# 03_-_28PINS_SCHEMATIC.net
KiCad netlist of a schematic drawn in Altium Designer
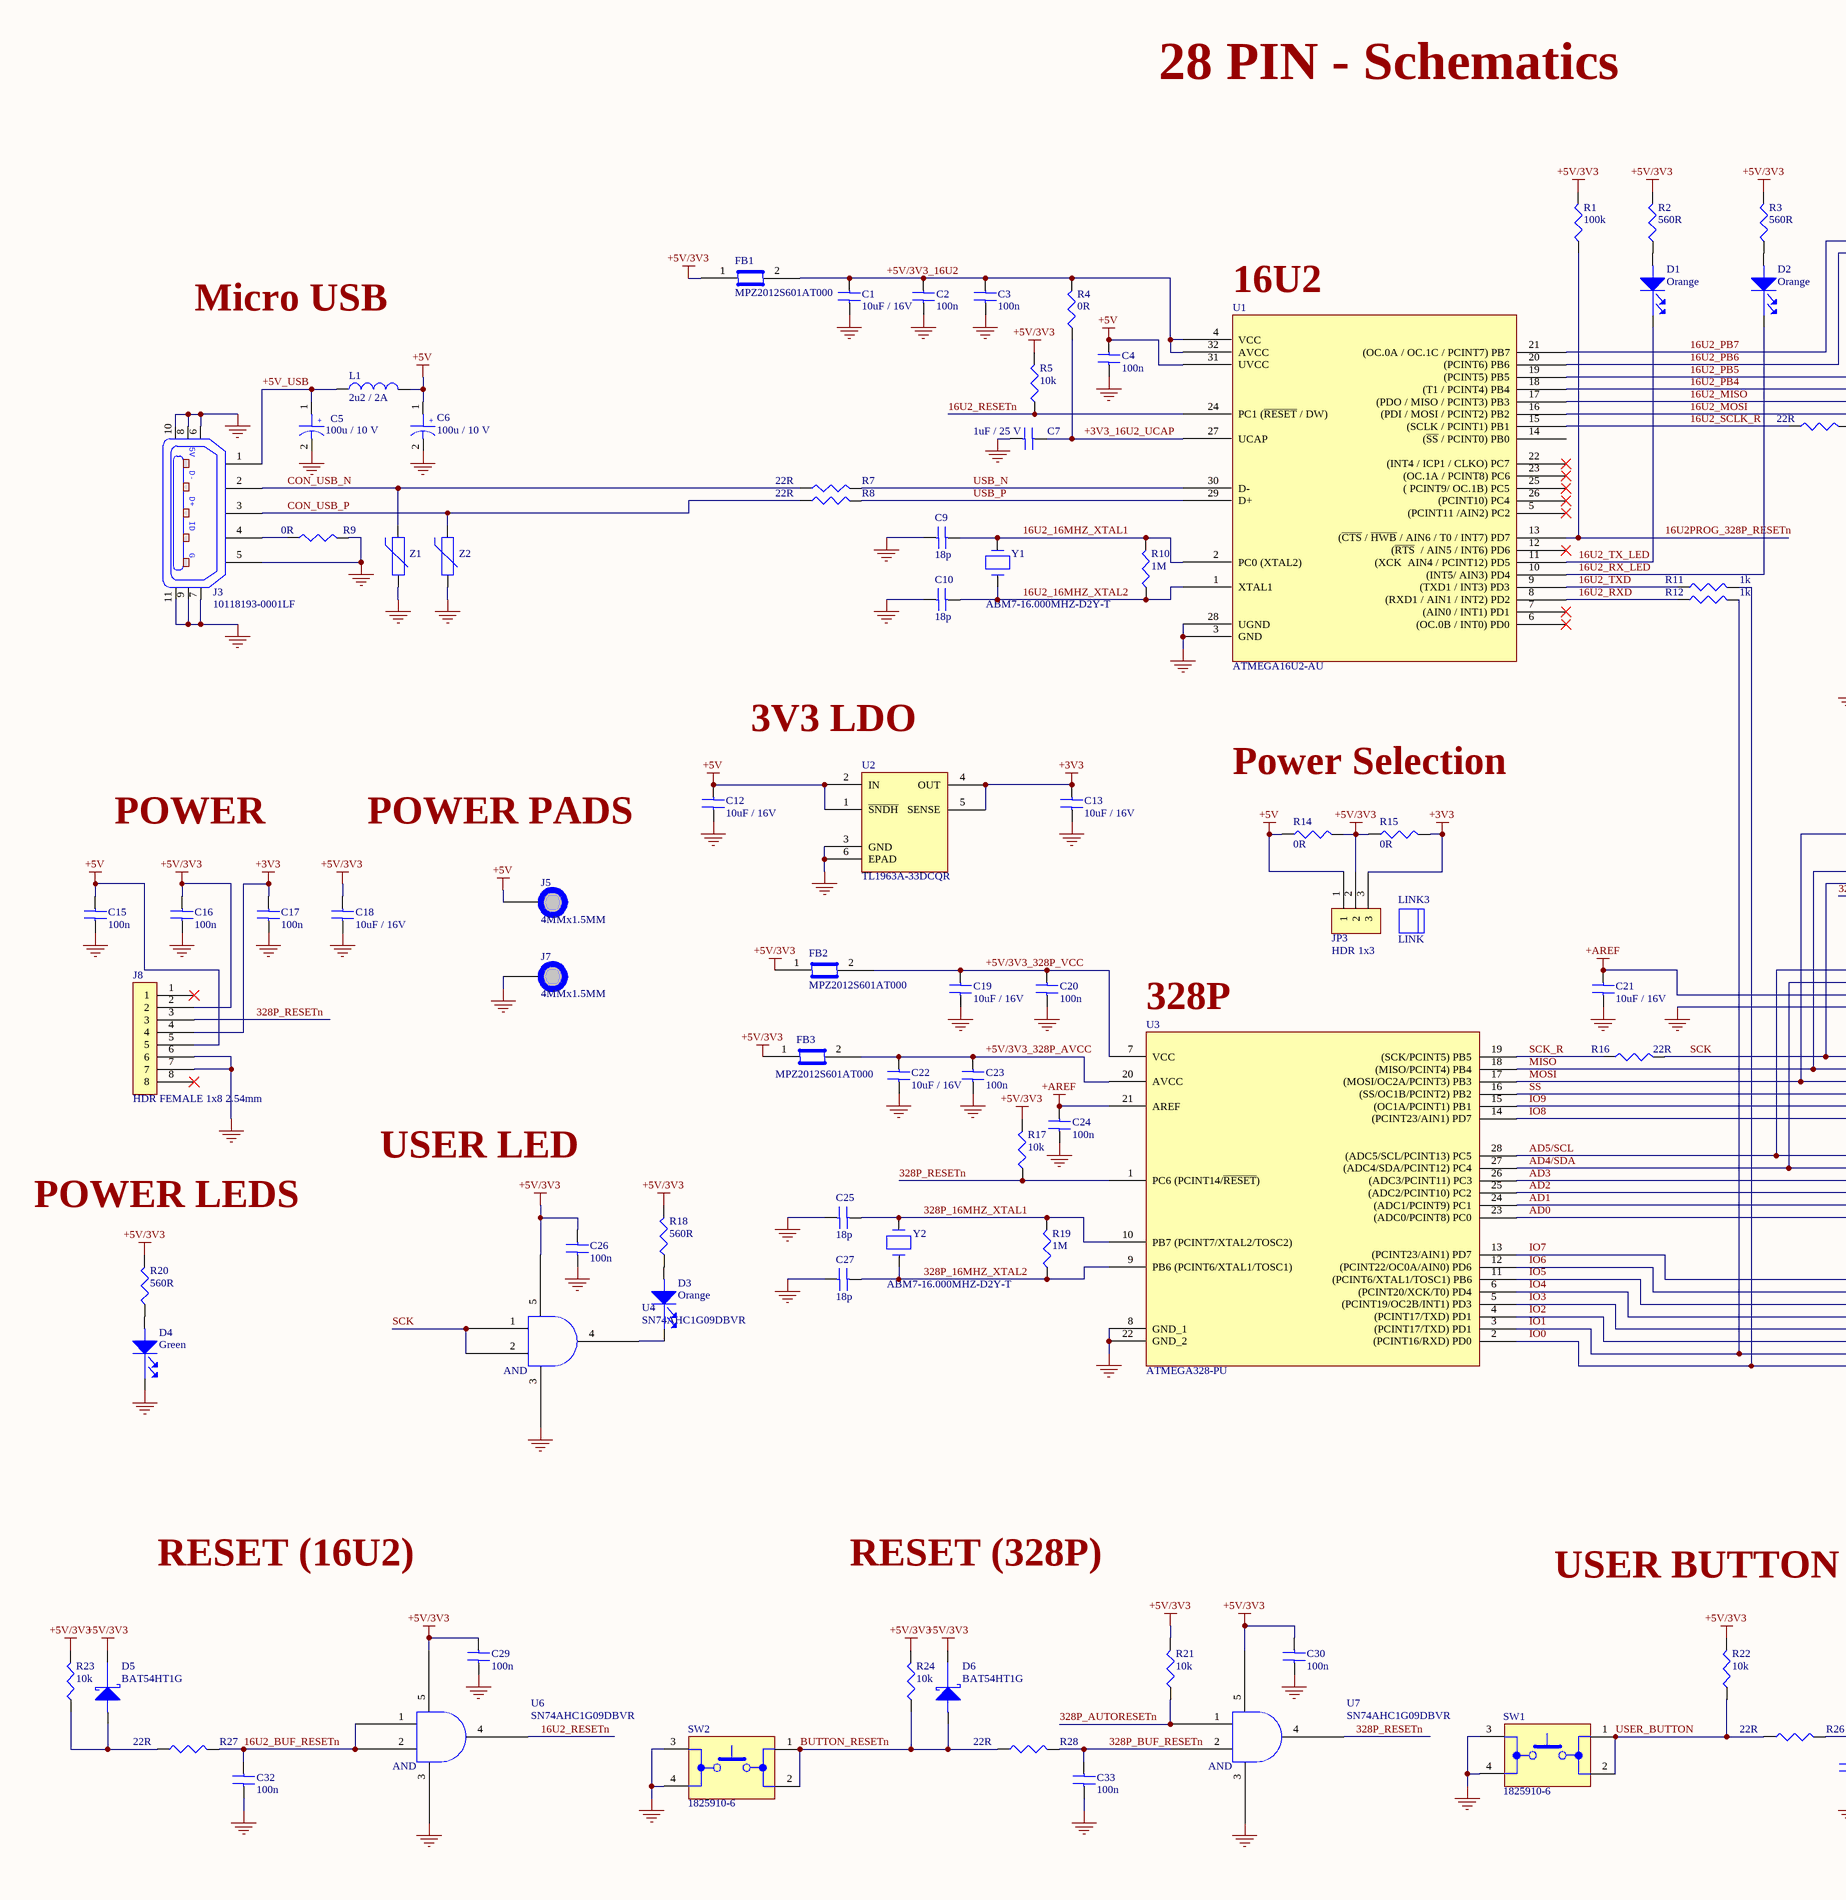
[diagram p0: [03] - 28PINS SCHEMATIC.SchDoc, left]
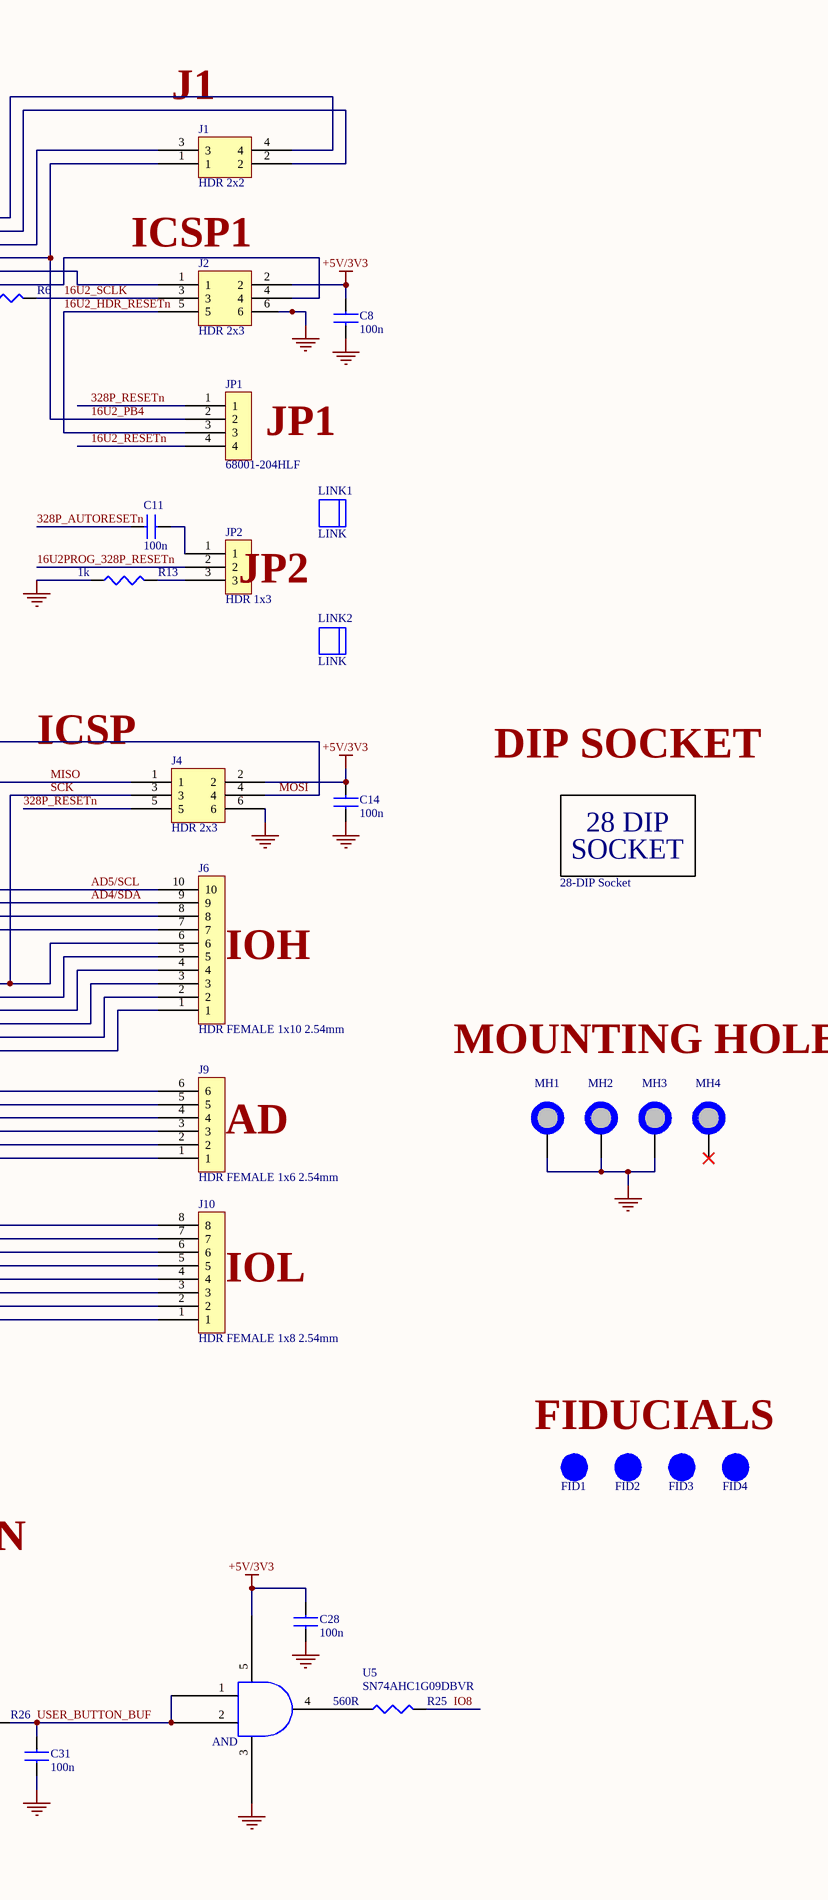
[diagram p1: [03] - 28PINS SCHEMATIC.SchDoc, right]

(export (version "E")
  (design (tool "Eeschema 10.0.6"))
  (components
    (comp (ref "C1")
      (value "10uF / 16V")
      (footprint "C0805")
      (fields
        (field (name "MANUFACTURER") "TDK")
        (field (name "MANUFACTURER PART NUMBER") "C2012X5R1C106M125AC")
        (field (name "TOLERANCE") "20%")
      )
      (libsource (lib "28_Pins_Project_V1I2") (part "C2012X5R1C106M125AC"))
    )
    (comp (ref "C2")
      (value "100n")
      (footprint "C0805")
      (fields
        (field (name "MANUFACTURER") "TDK")
        (field (name "MANUFACTURER PART NUMBER") "C2012X7R1H104K085AA")
        (field (name "TOLERANCE") "10%")
      )
      (libsource (lib "28_Pins_Project_V1I2") (part "C2012X7R1H104K085AA"))
    )
    (comp (ref "C3")
      (value "100n")
      (footprint "C0805")
      (fields
        (field (name "MANUFACTURER") "TDK")
        (field (name "MANUFACTURER PART NUMBER") "C2012X7R1H104K085AA")
        (field (name "TOLERANCE") "10%")
      )
      (libsource (lib "28_Pins_Project_V1I2") (part "C2012X7R1H104K085AA"))
    )
    (comp (ref "C4")
      (value "100n")
      (footprint "C0805")
      (fields
        (field (name "MANUFACTURER") "TDK")
        (field (name "MANUFACTURER PART NUMBER") "C2012X7R1H104K085AA")
        (field (name "TOLERANCE") "10%")
      )
      (libsource (lib "28_Pins_Project_V1I2") (part "C2012X7R1H104K085AA"))
    )
    (comp (ref "C5")
      (value "100u / 10 V")
      (footprint "C_ALU_C_SIZE")
      (description "CAP ALUM 100UF 20% 10V SMD")
      (fields
        (field (name "MANUFACTURER") "Panasonic")
        (field (name "MANUFACTURER PART NUMBER") "EEE-1AA101WR")
      )
      (libsource (lib "28_Pins_Project_V1I2") (part "EEE-1AA101WR"))
    )
    (comp (ref "C6")
      (value "100u / 10 V")
      (footprint "C_ALU_C_SIZE")
      (description "CAP ALUM 100UF 20% 10V SMD")
      (fields
        (field (name "MANUFACTURER") "Panasonic")
        (field (name "MANUFACTURER PART NUMBER") "EEE-1AA101WR")
      )
      (libsource (lib "28_Pins_Project_V1I2") (part "EEE-1AA101WR"))
    )
    (comp (ref "C7")
      (value "1uF / 25 V")
      (footprint "C0805")
      (fields
        (field (name "MANUFACTURER") "TDK")
        (field (name "MANUFACTURER PART NUMBER") "C2012X5R1E105K125AA")
        (field (name "TOLERANCE") "10%")
      )
      (libsource (lib "28_Pins_Project_V1I2") (part "C2012X5R1E105K125AA"))
    )
    (comp (ref "C8")
      (value "100n")
      (footprint "C0805")
      (fields
        (field (name "MANUFACTURER") "TDK")
        (field (name "MANUFACTURER PART NUMBER") "C2012X7R1H104K085AA")
        (field (name "TOLERANCE") "10%")
      )
      (libsource (lib "28_Pins_Project_V1I2") (part "C2012X7R1H104K085AA"))
    )
    (comp (ref "C9")
      (value "18p")
      (footprint "C0805")
      (description "CAP CER 18PF 50V C0G/NP0 0805")
      (fields
        (field (name "MANUFACTURER") "KEMET")
        (field (name "MANUFACTURER PART NUMBER") "C0805C180J5GACTU")
      )
      (libsource (lib "28_Pins_Project_V1I2") (part "C0805C180J5GACTU"))
    )
    (comp (ref "C10")
      (value "18p")
      (footprint "C0805")
      (description "CAP CER 18PF 50V C0G/NP0 0805")
      (fields
        (field (name "MANUFACTURER") "KEMET")
        (field (name "MANUFACTURER PART NUMBER") "C0805C180J5GACTU")
      )
      (libsource (lib "28_Pins_Project_V1I2") (part "C0805C180J5GACTU"))
    )
    (comp (ref "C11")
      (value "100n")
      (footprint "C0805")
      (fields
        (field (name "MANUFACTURER") "TDK")
        (field (name "MANUFACTURER PART NUMBER") "C2012X7R1H104K085AA")
        (field (name "TOLERANCE") "10%")
      )
      (libsource (lib "28_Pins_Project_V1I2") (part "C2012X7R1H104K085AA"))
    )
    (comp (ref "C12")
      (value "10uF / 16V")
      (footprint "C0805")
      (fields
        (field (name "MANUFACTURER") "TDK")
        (field (name "MANUFACTURER PART NUMBER") "C2012X5R1C106M125AC")
        (field (name "TOLERANCE") "20%")
      )
      (libsource (lib "28_Pins_Project_V1I2") (part "C2012X5R1C106M125AC"))
    )
    (comp (ref "C13")
      (value "10uF / 16V")
      (footprint "C0805")
      (fields
        (field (name "MANUFACTURER") "TDK")
        (field (name "MANUFACTURER PART NUMBER") "C2012X5R1C106M125AC")
        (field (name "TOLERANCE") "20%")
      )
      (libsource (lib "28_Pins_Project_V1I2") (part "C2012X5R1C106M125AC"))
    )
    (comp (ref "C14")
      (value "100n")
      (footprint "C0805")
      (fields
        (field (name "MANUFACTURER") "TDK")
        (field (name "MANUFACTURER PART NUMBER") "C2012X7R1H104K085AA")
        (field (name "TOLERANCE") "10%")
      )
      (libsource (lib "28_Pins_Project_V1I2") (part "C2012X7R1H104K085AA"))
    )
    (comp (ref "C15")
      (value "100n")
      (footprint "C0805")
      (fields
        (field (name "MANUFACTURER") "TDK")
        (field (name "MANUFACTURER PART NUMBER") "C2012X7R1H104K085AA")
        (field (name "TOLERANCE") "10%")
      )
      (libsource (lib "28_Pins_Project_V1I2") (part "C2012X7R1H104K085AA"))
    )
    (comp (ref "C16")
      (value "100n")
      (footprint "C0805")
      (fields
        (field (name "MANUFACTURER") "TDK")
        (field (name "MANUFACTURER PART NUMBER") "C2012X7R1H104K085AA")
        (field (name "TOLERANCE") "10%")
      )
      (libsource (lib "28_Pins_Project_V1I2") (part "C2012X7R1H104K085AA"))
    )
    (comp (ref "C17")
      (value "100n")
      (footprint "C0805")
      (fields
        (field (name "MANUFACTURER") "TDK")
        (field (name "MANUFACTURER PART NUMBER") "C2012X7R1H104K085AA")
        (field (name "TOLERANCE") "10%")
      )
      (libsource (lib "28_Pins_Project_V1I2") (part "C2012X7R1H104K085AA"))
    )
    (comp (ref "C18")
      (value "10uF / 16V")
      (footprint "C0805")
      (fields
        (field (name "MANUFACTURER") "TDK")
        (field (name "MANUFACTURER PART NUMBER") "C2012X5R1C106M125AC")
        (field (name "TOLERANCE") "20%")
      )
      (libsource (lib "28_Pins_Project_V1I2") (part "C2012X5R1C106M125AC"))
    )
    (comp (ref "C19")
      (value "10uF / 16V")
      (footprint "C0805")
      (fields
        (field (name "MANUFACTURER") "TDK")
        (field (name "MANUFACTURER PART NUMBER") "C2012X5R1C106M125AC")
        (field (name "TOLERANCE") "20%")
      )
      (libsource (lib "28_Pins_Project_V1I2") (part "C2012X5R1C106M125AC"))
    )
    (comp (ref "C20")
      (value "100n")
      (footprint "C0805")
      (fields
        (field (name "MANUFACTURER") "TDK")
        (field (name "MANUFACTURER PART NUMBER") "C2012X7R1H104K085AA")
        (field (name "TOLERANCE") "10%")
      )
      (libsource (lib "28_Pins_Project_V1I2") (part "C2012X7R1H104K085AA"))
    )
    (comp (ref "C21")
      (value "10uF / 16V")
      (footprint "C0805")
      (fields
        (field (name "MANUFACTURER") "TDK")
        (field (name "MANUFACTURER PART NUMBER") "C2012X5R1C106M125AC")
        (field (name "TOLERANCE") "20%")
      )
      (libsource (lib "28_Pins_Project_V1I2") (part "C2012X5R1C106M125AC"))
    )
    (comp (ref "C22")
      (value "10uF / 16V")
      (footprint "C0805")
      (fields
        (field (name "MANUFACTURER") "TDK")
        (field (name "MANUFACTURER PART NUMBER") "C2012X5R1C106M125AC")
        (field (name "TOLERANCE") "20%")
      )
      (libsource (lib "28_Pins_Project_V1I2") (part "C2012X5R1C106M125AC"))
    )
    (comp (ref "C23")
      (value "100n")
      (footprint "C0805")
      (fields
        (field (name "MANUFACTURER") "TDK")
        (field (name "MANUFACTURER PART NUMBER") "C2012X7R1H104K085AA")
        (field (name "TOLERANCE") "10%")
      )
      (libsource (lib "28_Pins_Project_V1I2") (part "C2012X7R1H104K085AA"))
    )
    (comp (ref "C24")
      (value "100n")
      (footprint "C0805")
      (fields
        (field (name "MANUFACTURER") "TDK")
        (field (name "MANUFACTURER PART NUMBER") "C2012X7R1H104K085AA")
        (field (name "TOLERANCE") "10%")
      )
      (libsource (lib "28_Pins_Project_V1I2") (part "C2012X7R1H104K085AA"))
    )
    (comp (ref "C25")
      (value "18p")
      (footprint "C0805")
      (description "CAP CER 18PF 50V C0G/NP0 0805")
      (fields
        (field (name "MANUFACTURER") "KEMET")
        (field (name "MANUFACTURER PART NUMBER") "C0805C180J5GACTU")
      )
      (libsource (lib "28_Pins_Project_V1I2") (part "C0805C180J5GACTU"))
    )
    (comp (ref "C26")
      (value "100n")
      (footprint "C0805")
      (fields
        (field (name "MANUFACTURER") "TDK")
        (field (name "MANUFACTURER PART NUMBER") "C2012X7R1H104K085AA")
        (field (name "TOLERANCE") "10%")
      )
      (libsource (lib "28_Pins_Project_V1I2") (part "C2012X7R1H104K085AA"))
    )
    (comp (ref "C27")
      (value "18p")
      (footprint "C0805")
      (description "CAP CER 18PF 50V C0G/NP0 0805")
      (fields
        (field (name "MANUFACTURER") "KEMET")
        (field (name "MANUFACTURER PART NUMBER") "C0805C180J5GACTU")
      )
      (libsource (lib "28_Pins_Project_V1I2") (part "C0805C180J5GACTU"))
    )
    (comp (ref "C28")
      (value "100n")
      (footprint "C0805")
      (fields
        (field (name "MANUFACTURER") "TDK")
        (field (name "MANUFACTURER PART NUMBER") "C2012X7R1H104K085AA")
        (field (name "TOLERANCE") "10%")
      )
      (libsource (lib "28_Pins_Project_V1I2") (part "C2012X7R1H104K085AA"))
    )
    (comp (ref "C29")
      (value "100n")
      (footprint "C0805")
      (fields
        (field (name "MANUFACTURER") "TDK")
        (field (name "MANUFACTURER PART NUMBER") "C2012X7R1H104K085AA")
        (field (name "TOLERANCE") "10%")
      )
      (libsource (lib "28_Pins_Project_V1I2") (part "C2012X7R1H104K085AA"))
    )
    (comp (ref "C30")
      (value "100n")
      (footprint "C0805")
      (fields
        (field (name "MANUFACTURER") "TDK")
        (field (name "MANUFACTURER PART NUMBER") "C2012X7R1H104K085AA")
        (field (name "TOLERANCE") "10%")
      )
      (libsource (lib "28_Pins_Project_V1I2") (part "C2012X7R1H104K085AA"))
    )
    (comp (ref "C31")
      (value "100n")
      (footprint "C0805")
      (fields
        (field (name "MANUFACTURER") "TDK")
        (field (name "MANUFACTURER PART NUMBER") "C2012X7R1H104K085AA")
        (field (name "TOLERANCE") "10%")
      )
      (libsource (lib "28_Pins_Project_V1I2") (part "C2012X7R1H104K085AA"))
    )
    (comp (ref "C32")
      (value "100n")
      (footprint "C0805")
      (fields
        (field (name "MANUFACTURER") "TDK")
        (field (name "MANUFACTURER PART NUMBER") "C2012X7R1H104K085AA")
        (field (name "TOLERANCE") "10%")
      )
      (libsource (lib "28_Pins_Project_V1I2") (part "C2012X7R1H104K085AA"))
    )
    (comp (ref "C33")
      (value "100n")
      (footprint "C0805")
      (fields
        (field (name "MANUFACTURER") "TDK")
        (field (name "MANUFACTURER PART NUMBER") "C2012X7R1H104K085AA")
        (field (name "TOLERANCE") "10%")
      )
      (libsource (lib "28_Pins_Project_V1I2") (part "C2012X7R1H104K085AA"))
    )
    (comp (ref "D1")
      (value "Orange")
      (footprint "LED_0603")
      (description "OSRAM - LO L29K-H2K1-24-Z - SMARTLED 0603 ORANGE 55AC2374")
      (fields
        (field (name "MANUFACTURER") "Osram Opto")
        (field (name "MANUFACTURER PART NUMBER") "LOL29K-H2K1-24-Z")
      )
      (libsource (lib "28_Pins_Project_V1I2") (part "LOL29K-H2K1-24-Z"))
    )
    (comp (ref "D2")
      (value "Orange")
      (footprint "LED_0603")
      (description "OSRAM - LO L29K-H2K1-24-Z - SMARTLED 0603 ORANGE 55AC2374")
      (fields
        (field (name "MANUFACTURER") "Osram Opto")
        (field (name "MANUFACTURER PART NUMBER") "LOL29K-H2K1-24-Z")
      )
      (libsource (lib "28_Pins_Project_V1I2") (part "LOL29K-H2K1-24-Z"))
    )
    (comp (ref "D3")
      (value "Orange")
      (footprint "LED_0603")
      (description "OSRAM - LO L29K-H2K1-24-Z - SMARTLED 0603 ORANGE 55AC2374")
      (fields
        (field (name "MANUFACTURER") "Osram Opto")
        (field (name "MANUFACTURER PART NUMBER") "LOL29K-H2K1-24-Z")
      )
      (libsource (lib "28_Pins_Project_V1I2") (part "LOL29K-H2K1-24-Z"))
    )
    (comp (ref "D4")
      (value "Green")
      (footprint "LED_0603")
      (description "LED Uni-Color Green 572nm 2-Pin Chip 0603(1608Metric) T/R")
      (fields
        (field (name "MANUFACTURER") "Osram Opto")
        (field (name "MANUFACTURER PART NUMBER") "LGL29K-G2J1-24-Z")
      )
      (libsource (lib "28_Pins_Project_V1I2") (part "LGL29K-G2J1-24-Z"))
    )
    (comp (ref "D5")
      (value "BAT54HT1G")
      (footprint "SOD323")
      (description "Small Signal Schottky Diode, Single, 30 V, 200 Ma, 800 Mv, 600 Ma, 150 C")
      (fields (field (name "MANUFACTURER") "ON Semiconductor / Fairchild"))
      (libsource (lib "28_Pins_Project_V1I2") (part "BAT54HT1G"))
    )
    (comp (ref "D6")
      (value "BAT54HT1G")
      (footprint "SOD323")
      (description "Small Signal Schottky Diode, Single, 30 V, 200 Ma, 800 Mv, 600 Ma, 150 C")
      (fields (field (name "MANUFACTURER") "ON Semiconductor / Fairchild"))
      (libsource (lib "28_Pins_Project_V1I2") (part "BAT54HT1G"))
    )
    (comp (ref "FB1")
      (value "MPZ2012S601AT000")
      (footprint "C0805")
      (description "Ferrite Beads Multi-Layer Power 600Ohm 25% 100MHz 2A 100mOhm DCR 0805 T/R")
      (fields (field (name "MANUFACTURER") "TDK"))
      (libsource (lib "28_Pins_Project_V1I2") (part "MPZ2012S601AT000"))
    )
    (comp (ref "FB2")
      (value "MPZ2012S601AT000")
      (footprint "C0805")
      (description "Ferrite Beads Multi-Layer Power 600Ohm 25% 100MHz 2A 100mOhm DCR 0805 T/R")
      (fields (field (name "MANUFACTURER") "TDK"))
      (libsource (lib "28_Pins_Project_V1I2") (part "MPZ2012S601AT000"))
    )
    (comp (ref "FB3")
      (value "MPZ2012S601AT000")
      (footprint "C0805")
      (description "Ferrite Beads Multi-Layer Power 600Ohm 25% 100MHz 2A 100mOhm DCR 0805 T/R")
      (fields (field (name "MANUFACTURER") "TDK"))
      (libsource (lib "28_Pins_Project_V1I2") (part "MPZ2012S601AT000"))
    )
    (comp (ref "FID1")
      (value "FID_1MMC")
      (footprint "FID_40X120D")
      (description "Fiducial 40mil Diameter, 120mil Mask")
      (libsource (lib "28_Pins_Project_V1I2") (part "FID_1MMC"))
    )
    (comp (ref "FID2")
      (value "FID_1MMC")
      (footprint "FID_40X120D")
      (description "Fiducial 40mil Diameter, 120mil Mask")
      (libsource (lib "28_Pins_Project_V1I2") (part "FID_1MMC"))
    )
    (comp (ref "FID3")
      (value "FID_1MMC")
      (footprint "FID_40X120D")
      (description "Fiducial 40mil Diameter, 120mil Mask")
      (libsource (lib "28_Pins_Project_V1I2") (part "FID_1MMC"))
    )
    (comp (ref "FID4")
      (value "FID_1MMC")
      (footprint "FID_40X120D")
      (description "Fiducial 40mil Diameter, 120mil Mask")
      (libsource (lib "28_Pins_Project_V1I2") (part "FID_1MMC"))
    )
    (comp (ref "J1")
      (value "HDR 2x2")
      (footprint "HDR 2x2 2.54mm")
      (description "CONN HEADER 4POS .100 STR 15AU")
      (fields
        (field (name "MANUFACTURER") "Amphenol ICC / FCI")
        (field (name "MANUFACTURER PART NUMBER") "68602-204HLF")
      )
      (libsource (lib "28_Pins_Project_V1I2") (part "68602-204HLF"))
    )
    (comp (ref "J2")
      (value "HDR 2x3")
      (footprint "HDR 2x3 2.54mm")
      (description "Conn Unshrouded Header HDR 6 POS 2.54mm Solder ST Top Entry Thru-Hole BergStik® Bulk")
      (fields
        (field (name "MANUFACTURER") "Amphenol ICC / FCI")
        (field (name "MANUFACTURER PART NUMBER") "67997-106HLF")
      )
      (libsource (lib "28_Pins_Project_V1I2") (part "67997-106HLF"))
    )
    (comp (ref "J3")
      (value "10118193-0001LF")
      (footprint "10118193")
      (description "CONN USB MICRO B RECPT SMT R/A")
      (fields (field (name "MANUFACTURER") "Amphenol ICC / FCI"))
      (libsource (lib "28_Pins_Project_V1I2") (part "10118193-0001LF"))
    )
    (comp (ref "J4")
      (value "HDR 2x3")
      (footprint "HDR 2x3 2.54mm")
      (description "Conn Unshrouded Header HDR 6 POS 2.54mm Solder ST Top Entry Thru-Hole BergStik® Bulk")
      (fields
        (field (name "MANUFACTURER") "Amphenol ICC / FCI")
        (field (name "MANUFACTURER PART NUMBER") "67997-106HLF")
      )
      (libsource (lib "28_Pins_Project_V1I2") (part "67997-106HLF"))
    )
    (comp (ref "J5")
      (value "4MMx1.5MM")
      (footprint "PAD_WITH_HOLE_4MMx1.5MM")
      (description "Pad with a hole 4mm x 1.5mm")
      (libsource (lib "28_Pins_Project_V1I2") (part "PAD_WITH_HOLE_4MM_1.5MM"))
    )
    (comp (ref "J6")
      (value "HDR FEMALE 1x10 2.54mm")
      (footprint "Hdr_Female_1x10_2.54mm")
      (description "10-WAY SIL VERT SOCKET L/FREE")
      (fields (field (name "MANUFACTURER") "Harwin") (field (name "MANUFACTURER PART NUMBER") "M20-7821046"))
      (libsource (lib "28_Pins_Project_V1I2") (part "M20-7821046"))
    )
    (comp (ref "J7")
      (value "4MMx1.5MM")
      (footprint "PAD_WITH_HOLE_4MMx1.5MM")
      (description "Pad with a hole 4mm x 1.5mm")
      (libsource (lib "28_Pins_Project_V1I2") (part "PAD_WITH_HOLE_4MM_1.5MM"))
    )
    (comp (ref "J8")
      (value "HDR FEMALE 1x8 2.54mm")
      (footprint "Hdr_Female_1x8_2.54mm")
      (description "08-WAY SIL VERT SOCKET L/FREE")
      (fields (field (name "MANUFACTURER") "Harwin") (field (name "MANUFACTURER PART NUMBER") "M20-7820842"))
      (libsource (lib "") (part "M20-7820842_1"))
    )
    (comp (ref "J9")
      (value "HDR FEMALE 1x6 2.54mm")
      (footprint "Hdr_Female_1x6_2.54mm")
      (description "06-WAY SIL VERT SOCKET L/FREE")
      (fields (field (name "MANUFACTURER") "Harwin") (field (name "MANUFACTURER PART NUMBER") "M20-7820646"))
      (libsource (lib "28_Pins_Project_V1I2") (part "M20-7820646"))
    )
    (comp (ref "J10")
      (value "HDR FEMALE 1x8 2.54mm")
      (footprint "Hdr_Female_1x8_2.54mm")
      (description "08-WAY SIL VERT SOCKET L/FREE")
      (fields (field (name "MANUFACTURER") "Harwin") (field (name "MANUFACTURER PART NUMBER") "M20-7820842"))
      (libsource (lib "28_Pins_Project_V1I2") (part "M20-7820842"))
    )
    (comp (ref "JP1")
      (value "68001-204HLF")
      (footprint "Hdr_Female_1x4_2.54mm")
      (description "Board Connector, 4 Contact(s), 1 Row(s), Male, Straight, Solder Terminal")
      (fields (field (name "MANUFACTURER") "Amphenol ICC"))
      (libsource (lib "28_Pins_Project_V1I2") (part "68001-204HLF"))
    )
    (comp (ref "JP2")
      (value "HDR 1x3")
      (footprint "Hdr_Female_1x3_2.54mm")
      (fields
        (field (name "MANUFACTURER") "Amphenol ICC")
        (field (name "MANUFACTURER PART NUMBER") "68000-103HLF")
      )
      (libsource (lib "") (part "68000-103HLF_1"))
    )
    (comp (ref "JP3")
      (value "HDR 1x3")
      (footprint "Hdr_Female_1x3_2.54mm")
      (fields
        (field (name "MANUFACTURER") "Amphenol ICC")
        (field (name "MANUFACTURER PART NUMBER") "68000-103HLF")
      )
      (libsource (lib "28_Pins_Project_V1I2") (part "68000-103HLF"))
    )
    (comp (ref "L1")
      (value "2u2 / 2A")
      (footprint "C1210_IND")
      (description "KEMET         L1210R2R2MDWIT             Product Range:L-DWI Series")
      (fields
        (field (name "MANUFACTURER") "KEMET")
        (field (name "MANUFACTURER PART NUMBER") "L1210R2R2MDWIT")
      )
      (libsource (lib "28_Pins_Project_V1I2") (part "L1210R2R2MDWIT"))
    )
    (comp (ref "LINK1")
      (value "LINK")
      (description "CONN JUMPER SHORTING .100\" GOLD")
      (fields
        (field (name "MANUFACTURER") "Sullins")
        (field (name "MANUFACTURER PART NUMBER") "QPC02SXGN-RC")
      )
      (libsource (lib "28_Pins_Project_V1I2") (part "QPC02SXGN-RC"))
    )
    (comp (ref "LINK2")
      (value "LINK")
      (description "CONN JUMPER SHORTING .100\" GOLD")
      (fields
        (field (name "MANUFACTURER") "Sullins")
        (field (name "MANUFACTURER PART NUMBER") "QPC02SXGN-RC")
      )
      (libsource (lib "28_Pins_Project_V1I2") (part "QPC02SXGN-RC"))
    )
    (comp (ref "LINK3")
      (value "LINK")
      (description "CONN JUMPER SHORTING .100\" GOLD")
      (fields
        (field (name "MANUFACTURER") "Sullins")
        (field (name "MANUFACTURER PART NUMBER") "QPC02SXGN-RC")
      )
      (libsource (lib "28_Pins_Project_V1I2") (part "QPC02SXGN-RC"))
    )
    (comp (ref "MH1")
      (value "MH_7.4MMC_3.2MMD")
      (footprint "MH_7.4MMD_3.2MMD")
      (description "Mounting Hole 7.4mm Diameter, 3.2mm Drill")
      (libsource (lib "28_Pins_Project_V1I2") (part "MH_7.4MMC_3.2MMD"))
    )
    (comp (ref "MH2")
      (value "MH_7.4MMC_3.2MMD")
      (footprint "MH_7.4MMD_3.2MMD")
      (description "Mounting Hole 7.4mm Diameter, 3.2mm Drill")
      (libsource (lib "28_Pins_Project_V1I2") (part "MH_7.4MMC_3.2MMD"))
    )
    (comp (ref "MH3")
      (value "MH_7.4MMC_3.2MMD")
      (footprint "MH_7.4MMD_3.2MMD")
      (description "Mounting Hole 7.4mm Diameter, 3.2mm Drill")
      (libsource (lib "28_Pins_Project_V1I2") (part "MH_7.4MMC_3.2MMD"))
    )
    (comp (ref "MH4")
      (value "MH_7.4MMNC_3.2MMD")
      (footprint "MH_7.4MMD_3.2MMD_NON_COPPER_NPTH")
      (description "Hole 7.4mm Diameter (Non Copper), 3.2mm Drill NPTH")
      (libsource (lib "28_Pins_Project_V1I2") (part "MH_7.4MMNC_3.2MMD"))
    )
    (comp (ref "R1")
      (value "100k")
      (footprint "R0805")
      (description "Res Thick Film 0805 100K Ohm 1% 1/8W ±100ppm/°C Molded SMD Paper T/R")
      (fields
        (field (name "MANUFACTURER") "Yageo")
        (field (name "MANUFACTURER PART NUMBER") "RC0805FR-07100KL")
      )
      (libsource (lib "28_Pins_Project_V1I2") (part "RC0805FR-07100KL"))
    )
    (comp (ref "R2")
      (value "560R")
      (footprint "R0805")
      (description "Surface Mount Thick Film Resistor, RC Series, 560 ohm, 125 mW, - 1%, 150 V, 0805 [2012 Metric]")
      (fields
        (field (name "MANUFACTURER") "Yageo")
        (field (name "MANUFACTURER PART NUMBER") "RC0805FR-07560RL")
      )
      (libsource (lib "28_Pins_Project_V1I2") (part "RC0805FR-07560RL"))
    )
    (comp (ref "R3")
      (value "560R")
      (footprint "R0805")
      (description "Surface Mount Thick Film Resistor, RC Series, 560 ohm, 125 mW, - 1%, 150 V, 0805 [2012 Metric]")
      (fields
        (field (name "MANUFACTURER") "Yageo")
        (field (name "MANUFACTURER PART NUMBER") "RC0805FR-07560RL")
      )
      (libsource (lib "28_Pins_Project_V1I2") (part "RC0805FR-07560RL"))
    )
    (comp (ref "R4")
      (value "0R")
      (footprint "R0805")
      (description "Surface Mount Thick Film Resistor, RC Series, 125 mW, - 5%, 150 V, 0805 [2012 Metric]")
      (fields
        (field (name "MANUFACTURER") "Yageo")
        (field (name "MANUFACTURER PART NUMBER") "RC0805JR-070RL")
      )
      (libsource (lib "28_Pins_Project_V1I2") (part "RC0805JR-070RL"))
    )
    (comp (ref "R5")
      (value "10k")
      (footprint "R0805")
      (description "RES SMD 10K OHM 1% 1/8W 0805")
      (fields
        (field (name "MANUFACTURER") "Yageo")
        (field (name "MANUFACTURER PART NUMBER") "RC0805FR-0710KL")
      )
      (libsource (lib "28_Pins_Project_V1I2") (part "RC0805FR-0710KL"))
    )
    (comp (ref "R6")
      (value "22R")
      (footprint "R0805")
      (description "RES SMD 22 OHM 1% 1/8W 0805")
      (fields
        (field (name "MANUFACTURER") "Yageo")
        (field (name "MANUFACTURER PART NUMBER") "RC0805FR-0722RL")
      )
      (libsource (lib "28_Pins_Project_V1I2") (part "RC0805FR-0722RL"))
    )
    (comp (ref "R7")
      (value "22R")
      (footprint "R0805")
      (description "RES SMD 22 OHM 1% 1/8W 0805")
      (fields
        (field (name "MANUFACTURER") "Yageo")
        (field (name "MANUFACTURER PART NUMBER") "RC0805FR-0722RL")
      )
      (libsource (lib "28_Pins_Project_V1I2") (part "RC0805FR-0722RL"))
    )
    (comp (ref "R8")
      (value "22R")
      (footprint "R0805")
      (description "RES SMD 22 OHM 1% 1/8W 0805")
      (fields
        (field (name "MANUFACTURER") "Yageo")
        (field (name "MANUFACTURER PART NUMBER") "RC0805FR-0722RL")
      )
      (libsource (lib "28_Pins_Project_V1I2") (part "RC0805FR-0722RL"))
    )
    (comp (ref "R9")
      (value "0R")
      (footprint "R0805")
      (description "Surface Mount Thick Film Resistor, RC Series, 125 mW, - 5%, 150 V, 0805 [2012 Metric]")
      (fields
        (field (name "MANUFACTURER") "Yageo")
        (field (name "MANUFACTURER PART NUMBER") "RC0805JR-070RL")
      )
      (libsource (lib "28_Pins_Project_V1I2") (part "RC0805JR-070RL"))
    )
    (comp (ref "R10")
      (value "1M")
      (footprint "R0805")
      (fields
        (field (name "MANUFACTURER") "Yageo Phycomp")
        (field (name "MANUFACTURER PART NUMBER") "RC0805FR-071ML")
        (field (name "TOLERANCE") "1%")
      )
      (libsource (lib "28_Pins_Project_V1I2") (part "RC0805FR-071ML_1"))
    )
    (comp (ref "R11")
      (value "1k")
      (footprint "R0805")
      (description "RES SMD 1K OHM 1% 1/8W 0805")
      (fields
        (field (name "MANUFACTURER") "Yageo")
        (field (name "MANUFACTURER PART NUMBER") "RC0805FR-071KL")
      )
      (libsource (lib "28_Pins_Project_V1I2") (part "RC0805FR-071KL"))
    )
    (comp (ref "R12")
      (value "1k")
      (footprint "R0805")
      (description "RES SMD 1K OHM 1% 1/8W 0805")
      (fields
        (field (name "MANUFACTURER") "Yageo")
        (field (name "MANUFACTURER PART NUMBER") "RC0805FR-071KL")
      )
      (libsource (lib "28_Pins_Project_V1I2") (part "RC0805FR-071KL"))
    )
    (comp (ref "R13")
      (value "1k")
      (footprint "R0805")
      (description "RES SMD 1K OHM 1% 1/8W 0805")
      (fields
        (field (name "MANUFACTURER") "Yageo")
        (field (name "MANUFACTURER PART NUMBER") "RC0805FR-071KL")
      )
      (libsource (lib "28_Pins_Project_V1I2") (part "RC0805FR-071KL"))
    )
    (comp (ref "R14")
      (value "0R")
      (footprint "R0805")
      (description "Surface Mount Thick Film Resistor, RC Series, 125 mW, - 5%, 150 V, 0805 [2012 Metric]")
      (fields
        (field (name "MANUFACTURER") "Yageo")
        (field (name "MANUFACTURER PART NUMBER") "RC0805JR-070RL")
      )
      (libsource (lib "28_Pins_Project_V1I2") (part "RC0805JR-070RL"))
    )
    (comp (ref "R15")
      (value "0R")
      (footprint "R0805")
      (description "Surface Mount Thick Film Resistor, RC Series, 125 mW, - 5%, 150 V, 0805 [2012 Metric]")
      (fields
        (field (name "MANUFACTURER") "Yageo")
        (field (name "MANUFACTURER PART NUMBER") "RC0805JR-070RL")
      )
      (libsource (lib "28_Pins_Project_V1I2") (part "RC0805JR-070RL"))
    )
    (comp (ref "R16")
      (value "22R")
      (footprint "R0805")
      (description "RES SMD 22 OHM 1% 1/8W 0805")
      (fields
        (field (name "MANUFACTURER") "Yageo")
        (field (name "MANUFACTURER PART NUMBER") "RC0805FR-0722RL")
      )
      (libsource (lib "28_Pins_Project_V1I2") (part "RC0805FR-0722RL"))
    )
    (comp (ref "R17")
      (value "10k")
      (footprint "R0805")
      (description "RES SMD 10K OHM 1% 1/8W 0805")
      (fields
        (field (name "MANUFACTURER") "Yageo")
        (field (name "MANUFACTURER PART NUMBER") "RC0805FR-0710KL")
      )
      (libsource (lib "28_Pins_Project_V1I2") (part "RC0805FR-0710KL"))
    )
    (comp (ref "R18")
      (value "560R")
      (footprint "R0805")
      (description "Surface Mount Thick Film Resistor, RC Series, 560 ohm, 125 mW, - 1%, 150 V, 0805 [2012 Metric]")
      (fields
        (field (name "MANUFACTURER") "Yageo")
        (field (name "MANUFACTURER PART NUMBER") "RC0805FR-07560RL")
      )
      (libsource (lib "28_Pins_Project_V1I2") (part "RC0805FR-07560RL"))
    )
    (comp (ref "R19")
      (value "1M")
      (footprint "R0805")
      (fields
        (field (name "MANUFACTURER") "Yageo Phycomp")
        (field (name "MANUFACTURER PART NUMBER") "RC0805FR-071ML")
        (field (name "TOLERANCE") "1%")
      )
      (libsource (lib "28_Pins_Project_V1I2") (part "RC0805FR-071ML_1"))
    )
    (comp (ref "R20")
      (value "560R")
      (footprint "R0805")
      (description "Surface Mount Thick Film Resistor, RC Series, 560 ohm, 125 mW, - 1%, 150 V, 0805 [2012 Metric]")
      (fields
        (field (name "MANUFACTURER") "Yageo")
        (field (name "MANUFACTURER PART NUMBER") "RC0805FR-07560RL")
      )
      (libsource (lib "28_Pins_Project_V1I2") (part "RC0805FR-07560RL"))
    )
    (comp (ref "R21")
      (value "10k")
      (footprint "R0805")
      (description "RES SMD 10K OHM 1% 1/8W 0805")
      (fields
        (field (name "MANUFACTURER") "Yageo")
        (field (name "MANUFACTURER PART NUMBER") "RC0805FR-0710KL")
      )
      (libsource (lib "28_Pins_Project_V1I2") (part "RC0805FR-0710KL"))
    )
    (comp (ref "R22")
      (value "10k")
      (footprint "R0805")
      (description "RES SMD 10K OHM 1% 1/8W 0805")
      (fields
        (field (name "MANUFACTURER") "Yageo")
        (field (name "MANUFACTURER PART NUMBER") "RC0805FR-0710KL")
      )
      (libsource (lib "28_Pins_Project_V1I2") (part "RC0805FR-0710KL"))
    )
    (comp (ref "R23")
      (value "10k")
      (footprint "R0805")
      (description "RES SMD 10K OHM 1% 1/8W 0805")
      (fields
        (field (name "MANUFACTURER") "Yageo")
        (field (name "MANUFACTURER PART NUMBER") "RC0805FR-0710KL")
      )
      (libsource (lib "28_Pins_Project_V1I2") (part "RC0805FR-0710KL"))
    )
    (comp (ref "R24")
      (value "10k")
      (footprint "R0805")
      (description "RES SMD 10K OHM 1% 1/8W 0805")
      (fields
        (field (name "MANUFACTURER") "Yageo")
        (field (name "MANUFACTURER PART NUMBER") "RC0805FR-0710KL")
      )
      (libsource (lib "28_Pins_Project_V1I2") (part "RC0805FR-0710KL"))
    )
    (comp (ref "R25")
      (value "560R")
      (footprint "R0805")
      (description "Surface Mount Thick Film Resistor, RC Series, 560 ohm, 125 mW, - 1%, 150 V, 0805 [2012 Metric]")
      (fields
        (field (name "MANUFACTURER") "Yageo")
        (field (name "MANUFACTURER PART NUMBER") "RC0805FR-07560RL")
      )
      (libsource (lib "28_Pins_Project_V1I2") (part "RC0805FR-07560RL"))
    )
    (comp (ref "R26")
      (value "22R")
      (footprint "R0805")
      (description "RES SMD 22 OHM 1% 1/8W 0805")
      (fields
        (field (name "MANUFACTURER") "Yageo")
        (field (name "MANUFACTURER PART NUMBER") "RC0805FR-0722RL")
      )
      (libsource (lib "28_Pins_Project_V1I2") (part "RC0805FR-0722RL"))
    )
    (comp (ref "R27")
      (value "22R")
      (footprint "R0805")
      (description "RES SMD 22 OHM 1% 1/8W 0805")
      (fields
        (field (name "MANUFACTURER") "Yageo")
        (field (name "MANUFACTURER PART NUMBER") "RC0805FR-0722RL")
      )
      (libsource (lib "28_Pins_Project_V1I2") (part "RC0805FR-0722RL"))
    )
    (comp (ref "R28")
      (value "22R")
      (footprint "R0805")
      (description "RES SMD 22 OHM 1% 1/8W 0805")
      (fields
        (field (name "MANUFACTURER") "Yageo")
        (field (name "MANUFACTURER PART NUMBER") "RC0805FR-0722RL")
      )
      (libsource (lib "28_Pins_Project_V1I2") (part "RC0805FR-0722RL"))
    )
    (comp (ref "SCKT FOR U1")
      (value "28-DIP Socket")
      (footprint "28_DIP_7.62mm_SOCKET")
      (description "CONN IC DIP SOCKET 28POS TIN")
      (fields (field (name "MANUFACTURER") "3M") (field (name "MANUFACTURER PART NUMBER") "4828-3004-CP"))
      (libsource (lib "28_Pins_Project_V1I2") (part "4828-3004-CP"))
    )
    (comp (ref "SW1")
      (value "1825910-6")
      (footprint "1825910-6")
      (description "6X6, H5,  160G TAC.SWITCH")
      (fields (field (name "MANUFACTURER") "TE Connectivity Alcoswitch"))
      (libsource (lib "28_Pins_Project_V1I2") (part "1825910-6"))
    )
    (comp (ref "SW2")
      (value "1825910-6")
      (footprint "1825910-6")
      (description "6X6, H5,  160G TAC.SWITCH")
      (fields (field (name "MANUFACTURER") "TE Connectivity Alcoswitch"))
      (libsource (lib "28_Pins_Project_V1I2") (part "1825910-6"))
    )
    (comp (ref "U1")
      (value "ATMEGA16U2-AU")
      (footprint "TQFP32")
      (description "ATmega Series 16 KB Flash 512 B RAM 16 MHz 8-Bit Microcontroller - TQFP-32")
      (fields (field (name "MANUFACTURER") "Microchip / Atmel"))
      (libsource (lib "28_Pins_Project_V1I2") (part "ATMEGA16U2-AU"))
    )
    (comp (ref "U2")
      (value "TL1963A-33DCQR")
      (footprint "DCQ (R-PDSO-G6)")
      (description "IC REG LINEAR 3.3V 1.5A SOT223-6")
      (fields (field (name "MANUFACTURER") "Texas Instruments"))
      (libsource (lib "28_Pins_Project_V1I2") (part "TL1963A-33DCQR"))
    )
    (comp (ref "U3")
      (value "ATMEGA328-PU")
      (footprint "28_DIP_7.62mm")
      (description "MCU 8-bit ATmega AVR RISC 32KB Flash 2.5V/3.3V/5V 28-Pin PDIP")
      (fields (field (name "MANUFACTURER") "Microchip / Atmel"))
      (libsource (lib "28_Pins_Project_V1I2") (part "ATMEGA328-PU"))
    )
    (comp (ref "U4")
      (value "SN74AHC1G09DBVR")
      (footprint "DBV_SOT_23_5")
      (description "TEXAS INSTRUMENTS - SN74AHC1G09DBVR - AND Gate, 74AHC1G09, 2 Input, 2 V to 5.5 V, SOT-23-5")
      (fields (field (name "MANUFACTURER") "Texas Instruments"))
      (libsource (lib "28_Pins_Project_V1I2") (part "SN74AHC1G09DBVR"))
    )
    (comp (ref "U5")
      (value "SN74AHC1G09DBVR")
      (footprint "DBV_SOT_23_5")
      (description "TEXAS INSTRUMENTS - SN74AHC1G09DBVR - AND Gate, 74AHC1G09, 2 Input, 2 V to 5.5 V, SOT-23-5")
      (fields (field (name "MANUFACTURER") "Texas Instruments"))
      (libsource (lib "28_Pins_Project_V1I2") (part "SN74AHC1G09DBVR"))
    )
    (comp (ref "U6")
      (value "SN74AHC1G09DBVR")
      (footprint "DBV_SOT_23_5")
      (description "TEXAS INSTRUMENTS - SN74AHC1G09DBVR - AND Gate, 74AHC1G09, 2 Input, 2 V to 5.5 V, SOT-23-5")
      (fields (field (name "MANUFACTURER") "Texas Instruments"))
      (libsource (lib "28_Pins_Project_V1I2") (part "SN74AHC1G09DBVR"))
    )
    (comp (ref "U7")
      (value "SN74AHC1G09DBVR")
      (footprint "DBV_SOT_23_5")
      (description "TEXAS INSTRUMENTS - SN74AHC1G09DBVR - AND Gate, 74AHC1G09, 2 Input, 2 V to 5.5 V, SOT-23-5")
      (fields (field (name "MANUFACTURER") "Texas Instruments"))
      (libsource (lib "28_Pins_Project_V1I2") (part "SN74AHC1G09DBVR"))
    )
    (comp (ref "Y1")
      (value "ABM7-16.000MHZ-D2Y-T")
      (footprint "ABM7_v1_1_BIG")
      (description "CRYSTAL 16.0000MHZ 18PF SMD")
      (fields (field (name "MANUFACTURER") "Abracon") (field (name "TOLERANCE") "20ppm"))
      (libsource (lib "28_Pins_Project_V1I2") (part "ABM7-16.000MHZ-D2Y-T"))
    )
    (comp (ref "Y2")
      (value "ABM7-16.000MHZ-D2Y-T")
      (footprint "ABM7_v1_1_BIG")
      (description "CRYSTAL 16.0000MHZ 18PF SMD")
      (fields (field (name "MANUFACTURER") "Abracon") (field (name "TOLERANCE") "20ppm"))
      (libsource (lib "28_Pins_Project_V1I2") (part "ABM7-16.000MHZ-D2Y-T"))
    )
    (comp (ref "Z1")
      (value "CG0603MLC-05E")
      (footprint "R0603")
      (description "VARISTOR 0603")
      (fields (field (name "MANUFACTURER") "Bourns") (field (name "VOLTAGE") "5V"))
      (libsource (lib "28_Pins_Project_V1I2") (part "CG0603MLC-05E"))
    )
    (comp (ref "Z2")
      (value "CG0603MLC-05E")
      (footprint "R0603")
      (description "VARISTOR 0603")
      (fields (field (name "MANUFACTURER") "Bourns") (field (name "VOLTAGE") "5V"))
      (libsource (lib "28_Pins_Project_V1I2") (part "CG0603MLC-05E"))
    )
  )
  (nets
    (net (code "1") (name "+3V3") (class "Default")
      (node (ref "C13") (pin "1") (pinfunction "1_1") (pintype "passive"))
      (node (ref "C17") (pin "2") (pinfunction "2_2") (pintype "passive"))
      (node (ref "J8") (pin "4") (pinfunction "4_4") (pintype "passive"))
      (node (ref "JP3") (pin "3") (pinfunction "3_3") (pintype "passive"))
      (node (ref "R15") (pin "2") (pinfunction "2_2") (pintype "passive"))
      (node (ref "U2") (pin "4") (pinfunction "OUT_4") (pintype "passive"))
      (node (ref "U2") (pin "5") (pinfunction "SENSE_5") (pintype "passive"))
    )
    (net (code "2") (name "+5V") (class "Default")
      (node (ref "C12") (pin "2") (pinfunction "2_2") (pintype "passive"))
      (node (ref "C15") (pin "2") (pinfunction "2_2") (pintype "passive"))
      (node (ref "C4") (pin "2") (pinfunction "2_2") (pintype "passive"))
      (node (ref "C6") (pin "1") (pinfunction "1_1") (pintype "passive"))
      (node (ref "J5") (pin "1") (pinfunction "1_1") (pintype "passive"))
      (node (ref "J8") (pin "5") (pinfunction "5_5") (pintype "passive"))
      (node (ref "JP3") (pin "1") (pinfunction "1_1") (pintype "passive"))
      (node (ref "L1") (pin "2") (pinfunction "2_2") (pintype "passive"))
      (node (ref "R14") (pin "1") (pinfunction "1_1") (pintype "passive"))
      (node (ref "U1") (pin "31") (pinfunction "UVCC_31") (pintype "passive"))
      (node (ref "U2") (pin "1") (pinfunction "~{SNDH}_1") (pintype "passive"))
      (node (ref "U2") (pin "2") (pinfunction "IN_2") (pintype "passive"))
    )
    (net (code "3") (name "+5V{slash}3V3") (class "Default")
      (node (ref "C14") (pin "2") (pinfunction "2_2") (pintype "passive"))
      (node (ref "C16") (pin "2") (pinfunction "2_2") (pintype "passive"))
      (node (ref "C18") (pin "2") (pinfunction "2_2") (pintype "passive"))
      (node (ref "C26") (pin "2") (pinfunction "2_2") (pintype "passive"))
      (node (ref "C28") (pin "2") (pinfunction "2_2") (pintype "passive"))
      (node (ref "C29") (pin "2") (pinfunction "2_2") (pintype "passive"))
      (node (ref "C30") (pin "2") (pinfunction "2_2") (pintype "passive"))
      (node (ref "C8") (pin "2") (pinfunction "2_2") (pintype "passive"))
      (node (ref "D5") (pin "1") (pinfunction "Cathode_1") (pintype "passive"))
      (node (ref "D6") (pin "1") (pinfunction "Cathode_1") (pintype "passive"))
      (node (ref "FB1") (pin "1") (pinfunction "1_1") (pintype "passive"))
      (node (ref "FB2") (pin "1") (pinfunction "1_1") (pintype "passive"))
      (node (ref "FB3") (pin "1") (pinfunction "1_1") (pintype "passive"))
      (node (ref "J2") (pin "2") (pinfunction "2_2") (pintype "passive"))
      (node (ref "J4") (pin "2") (pinfunction "2_2") (pintype "passive"))
      (node (ref "J8") (pin "2") (pinfunction "2_2") (pintype "passive"))
      (node (ref "JP3") (pin "2") (pinfunction "2_2") (pintype "passive"))
      (node (ref "R1") (pin "2") (pinfunction "2_2") (pintype "passive"))
      (node (ref "R14") (pin "2") (pinfunction "2_2") (pintype "passive"))
      (node (ref "R15") (pin "1") (pinfunction "1_1") (pintype "passive"))
      (node (ref "R17") (pin "2") (pinfunction "2_2") (pintype "passive"))
      (node (ref "R18") (pin "2") (pinfunction "2_2") (pintype "passive"))
      (node (ref "R2") (pin "2") (pinfunction "2_2") (pintype "passive"))
      (node (ref "R20") (pin "2") (pinfunction "2_2") (pintype "passive"))
      (node (ref "R21") (pin "2") (pinfunction "2_2") (pintype "passive"))
      (node (ref "R22") (pin "2") (pinfunction "2_2") (pintype "passive"))
      (node (ref "R23") (pin "2") (pinfunction "2_2") (pintype "passive"))
      (node (ref "R24") (pin "2") (pinfunction "2_2") (pintype "passive"))
      (node (ref "R3") (pin "2") (pinfunction "2_2") (pintype "passive"))
      (node (ref "R5") (pin "2") (pinfunction "2_2") (pintype "passive"))
      (node (ref "U4") (pin "5") (pinfunction "5_5") (pintype "passive"))
      (node (ref "U5") (pin "5") (pinfunction "5_5") (pintype "passive"))
      (node (ref "U6") (pin "5") (pinfunction "5_5") (pintype "passive"))
      (node (ref "U7") (pin "5") (pinfunction "5_5") (pintype "passive"))
    )
    (net (code "4") (name "+AREF") (class "Default")
      (node (ref "C21") (pin "2") (pinfunction "2_2") (pintype "passive"))
      (node (ref "C24") (pin "2") (pinfunction "2_2") (pintype "passive"))
      (node (ref "J6") (pin "8") (pinfunction "8_8") (pintype "passive"))
      (node (ref "U3") (pin "21") (pinfunction "AREF_21") (pintype "passive"))
    )
    (net (code "5") (name "/+3V3_16U2_UCAP") (class "Default")
      (node (ref "C7") (pin "2") (pinfunction "2_2") (pintype "passive"))
      (node (ref "R4") (pin "1") (pinfunction "1_1") (pintype "passive"))
      (node (ref "U1") (pin "27") (pinfunction "UCAP_27") (pintype "passive"))
    )
    (net (code "6") (name "/+5V_USB") (class "Default")
      (node (ref "C5") (pin "1") (pinfunction "1_1") (pintype "passive"))
      (node (ref "J3") (pin "1") (pinfunction "1_1") (pintype "passive"))
      (node (ref "L1") (pin "1") (pinfunction "1_1") (pintype "passive"))
    )
    (net (code "7") (name "/+5V{slash}3V3_16U2") (class "Default")
      (node (ref "C1") (pin "1") (pinfunction "1_1") (pintype "passive"))
      (node (ref "C2") (pin "1") (pinfunction "1_1") (pintype "passive"))
      (node (ref "C3") (pin "1") (pinfunction "1_1") (pintype "passive"))
      (node (ref "FB1") (pin "2") (pinfunction "2_2") (pintype "passive"))
      (node (ref "R4") (pin "2") (pinfunction "2_2") (pintype "passive"))
      (node (ref "U1") (pin "32") (pinfunction "AVCC_32") (pintype "passive"))
      (node (ref "U1") (pin "4") (pinfunction "VCC_4") (pintype "passive"))
    )
    (net (code "8") (name "/+5V{slash}3V3_328P_AVCC") (class "Default")
      (node (ref "C22") (pin "2") (pinfunction "2_2") (pintype "passive"))
      (node (ref "C23") (pin "2") (pinfunction "2_2") (pintype "passive"))
      (node (ref "FB3") (pin "2") (pinfunction "2_2") (pintype "passive"))
      (node (ref "U3") (pin "20") (pinfunction "AVCC_20") (pintype "passive"))
    )
    (net (code "9") (name "/+5V{slash}3V3_328P_VCC") (class "Default")
      (node (ref "C19") (pin "2") (pinfunction "2_2") (pintype "passive"))
      (node (ref "C20") (pin "2") (pinfunction "2_2") (pintype "passive"))
      (node (ref "FB2") (pin "2") (pinfunction "2_2") (pintype "passive"))
      (node (ref "U3") (pin "7") (pinfunction "VCC_7") (pintype "passive"))
    )
    (net (code "10") (name "/16U2PROG_328P_RESETn") (class "Default")
      (node (ref "JP2") (pin "2") (pinfunction "2_2") (pintype "passive"))
      (node (ref "R1") (pin "1") (pinfunction "1_1") (pintype "passive"))
      (node (ref "U1") (pin "13") (pinfunction "(~{CTS}_/_~{HWB}_/_AIN6_/_T0_/_INT7)_PD7_13") (pintype "passive"))
    )
    (net (code "11") (name "/16U2_16MHZ_XTAL1") (class "Default")
      (node (ref "C9") (pin "2") (pinfunction "2_2") (pintype "passive"))
      (node (ref "R10") (pin "2") (pinfunction "2_2") (pintype "passive"))
      (node (ref "U1") (pin "2") (pinfunction "PC0_(XTAL2)_2") (pintype "passive"))
      (node (ref "Y1") (pin "2") (pinfunction "2_2") (pintype "passive"))
    )
    (net (code "12") (name "/16U2_16MHZ_XTAL2") (class "Default")
      (node (ref "C10") (pin "2") (pinfunction "2_2") (pintype "passive"))
      (node (ref "R10") (pin "1") (pinfunction "1_1") (pintype "passive"))
      (node (ref "U1") (pin "1") (pinfunction "XTAL1_1") (pintype "passive"))
      (node (ref "Y1") (pin "1") (pinfunction "1_1") (pintype "passive"))
    )
    (net (code "13") (name "/16U2_BUF_RESETn") (class "Default")
      (node (ref "C32") (pin "2") (pinfunction "2_2") (pintype "passive"))
      (node (ref "R27") (pin "2") (pinfunction "2_2") (pintype "passive"))
      (node (ref "U6") (pin "1") (pinfunction "1_1") (pintype "passive"))
      (node (ref "U6") (pin "2") (pinfunction "2_2") (pintype "passive"))
    )
    (net (code "14") (name "/16U2_HDR_RESETn") (class "Default")
      (node (ref "J2") (pin "5") (pinfunction "5_5") (pintype "passive"))
      (node (ref "JP1") (pin "3") (pinfunction "3_3") (pintype "passive"))
    )
    (net (code "15") (name "/16U2_MISO") (class "Default")
      (node (ref "J2") (pin "1") (pinfunction "1_1") (pintype "passive"))
      (node (ref "U1") (pin "17") (pinfunction "(PDO_/_MISO_/_PCINT3)_PB3_17") (pintype "passive"))
    )
    (net (code "16") (name "/16U2_MOSI") (class "Default")
      (node (ref "J2") (pin "4") (pinfunction "4_4") (pintype "passive"))
      (node (ref "U1") (pin "16") (pinfunction "(PDI_/_MOSI_/_PCINT2)_PB2_16") (pintype "passive"))
    )
    (net (code "17") (name "/16U2_PB4") (class "Default")
      (node (ref "J1") (pin "1") (pinfunction "1_1") (pintype "passive"))
      (node (ref "JP1") (pin "2") (pinfunction "2_2") (pintype "passive"))
      (node (ref "U1") (pin "18") (pinfunction "(T1_/_PCINT4)_PB4_18") (pintype "passive"))
    )
    (net (code "18") (name "/16U2_PB5") (class "Default")
      (node (ref "J1") (pin "3") (pinfunction "3_3") (pintype "passive"))
      (node (ref "U1") (pin "19") (pinfunction "(PCINT5)_PB5_19") (pintype "passive"))
    )
    (net (code "19") (name "/16U2_PB6") (class "Default")
      (node (ref "J1") (pin "2") (pinfunction "2_2") (pintype "passive"))
      (node (ref "U1") (pin "20") (pinfunction "(PCINT6)_PB6_20") (pintype "passive"))
    )
    (net (code "20") (name "/16U2_PB7") (class "Default")
      (node (ref "J1") (pin "4") (pinfunction "4_4") (pintype "passive"))
      (node (ref "U1") (pin "21") (pinfunction "(OC.0A_/_OC.1C_/_PCINT7)_PB7_21") (pintype "passive"))
    )
    (net (code "21") (name "/16U2_RESETn") (class "Default")
      (node (ref "JP1") (pin "4") (pinfunction "4_4") (pintype "passive"))
      (node (ref "R5") (pin "1") (pinfunction "1_1") (pintype "passive"))
      (node (ref "U1") (pin "24") (pinfunction "PC1_(~{RESET}_/_DW)_24") (pintype "passive"))
      (node (ref "U6") (pin "4") (pinfunction "4_4") (pintype "passive"))
    )
    (net (code "22") (name "/16U2_RXD") (class "Default")
      (node (ref "R12") (pin "1") (pinfunction "1_1") (pintype "passive"))
      (node (ref "U1") (pin "8") (pinfunction "(RXD1_/_AIN1_/_INT2)_PD2_8") (pintype "passive"))
    )
    (net (code "23") (name "/16U2_RX_LED") (class "Default")
      (node (ref "D2") (pin "1") (pinfunction "Cathode_1") (pintype "passive"))
      (node (ref "U1") (pin "10") (pinfunction "(INT5/_AIN3)_PD4_10") (pintype "passive"))
    )
    (net (code "24") (name "/16U2_SCLK") (class "Default")
      (node (ref "J2") (pin "3") (pinfunction "3_3") (pintype "passive"))
      (node (ref "R6") (pin "2") (pinfunction "2_2") (pintype "passive"))
    )
    (net (code "25") (name "/16U2_SCLK_R") (class "Default")
      (node (ref "R6") (pin "1") (pinfunction "1_1") (pintype "passive"))
      (node (ref "U1") (pin "15") (pinfunction "(SCLK_/_PCINT1)_PB1_15") (pintype "passive"))
    )
    (net (code "26") (name "/16U2_TXD") (class "Default")
      (node (ref "R11") (pin "1") (pinfunction "1_1") (pintype "passive"))
      (node (ref "U1") (pin "9") (pinfunction "(TXD1_/_INT3)_PD3_9") (pintype "passive"))
    )
    (net (code "27") (name "/16U2_TX_LED") (class "Default")
      (node (ref "D1") (pin "1") (pinfunction "Cathode_1") (pintype "passive"))
      (node (ref "U1") (pin "11") (pinfunction "(XCK__AIN4_/_PCINT12)_PD5_11") (pintype "passive"))
    )
    (net (code "28") (name "/328P_16MHZ_XTAL1") (class "Default")
      (node (ref "C25") (pin "2") (pinfunction "2_2") (pintype "passive"))
      (node (ref "R19") (pin "2") (pinfunction "2_2") (pintype "passive"))
      (node (ref "U3") (pin "10") (pinfunction "PB7_(PCINT7/XTAL2/TOSC2)_10") (pintype "passive"))
      (node (ref "Y2") (pin "2") (pinfunction "2_2") (pintype "passive"))
    )
    (net (code "29") (name "/328P_16MHZ_XTAL2") (class "Default")
      (node (ref "C27") (pin "2") (pinfunction "2_2") (pintype "passive"))
      (node (ref "R19") (pin "1") (pinfunction "1_1") (pintype "passive"))
      (node (ref "U3") (pin "9") (pinfunction "PB6_(PCINT6/XTAL1/TOSC1)_9") (pintype "passive"))
      (node (ref "Y2") (pin "1") (pinfunction "1_1") (pintype "passive"))
    )
    (net (code "30") (name "/328P_AUTORESETn") (class "Default")
      (node (ref "C11") (pin "1") (pinfunction "1_1") (pintype "passive"))
      (node (ref "R21") (pin "1") (pinfunction "1_1") (pintype "passive"))
      (node (ref "U7") (pin "1") (pinfunction "1_1") (pintype "passive"))
    )
    (net (code "31") (name "/328P_BUF_RESETn") (class "Default")
      (node (ref "C33") (pin "2") (pinfunction "2_2") (pintype "passive"))
      (node (ref "R28") (pin "2") (pinfunction "2_2") (pintype "passive"))
      (node (ref "U7") (pin "2") (pinfunction "2_2") (pintype "passive"))
    )
    (net (code "32") (name "/328P_RESETn") (class "Default")
      (node (ref "J4") (pin "5") (pinfunction "5_5") (pintype "passive"))
      (node (ref "J8") (pin "3") (pinfunction "3_3") (pintype "passive"))
      (node (ref "JP1") (pin "1") (pinfunction "1_1") (pintype "passive"))
      (node (ref "R17") (pin "1") (pinfunction "1_1") (pintype "passive"))
      (node (ref "U3") (pin "1") (pinfunction "PC6_(PCINT14/~{RESET})_1") (pintype "passive"))
      (node (ref "U7") (pin "4") (pinfunction "4_4") (pintype "passive"))
    )
    (net (code "33") (name "/AD0") (class "Default")
      (node (ref "J9") (pin "1") (pinfunction "1_1") (pintype "passive"))
      (node (ref "U3") (pin "23") (pinfunction "(ADC0/PCINT8)_PC0_23") (pintype "passive"))
    )
    (net (code "34") (name "/AD1") (class "Default")
      (node (ref "J9") (pin "2") (pinfunction "2_2") (pintype "passive"))
      (node (ref "U3") (pin "24") (pinfunction "(ADC1/PCINT9)_PC1_24") (pintype "passive"))
    )
    (net (code "35") (name "/AD2") (class "Default")
      (node (ref "J9") (pin "3") (pinfunction "3_3") (pintype "passive"))
      (node (ref "U3") (pin "25") (pinfunction "(ADC2/PCINT10)_PC2_25") (pintype "passive"))
    )
    (net (code "36") (name "/AD3") (class "Default")
      (node (ref "J9") (pin "4") (pinfunction "4_4") (pintype "passive"))
      (node (ref "U3") (pin "26") (pinfunction "(ADC3/PCINT11)_PC3_26") (pintype "passive"))
    )
    (net (code "37") (name "/AD4{slash}SDA") (class "Default")
      (node (ref "J6") (pin "9") (pinfunction "9_9") (pintype "passive"))
      (node (ref "J9") (pin "5") (pinfunction "5_5") (pintype "passive"))
      (node (ref "U3") (pin "27") (pinfunction "(ADC4/SDA/PCINT12)_PC4_27") (pintype "passive"))
    )
    (net (code "38") (name "/AD5{slash}SCL") (class "Default")
      (node (ref "J6") (pin "10") (pinfunction "10_10") (pintype "passive"))
      (node (ref "J9") (pin "6") (pinfunction "6_6") (pintype "passive"))
      (node (ref "U3") (pin "28") (pinfunction "(ADC5/SCL/PCINT13)_PC5_28") (pintype "passive"))
    )
    (net (code "39") (name "/BUTTON_RESETn") (class "Default")
      (node (ref "D6") (pin "2") (pinfunction "Anode_2") (pintype "passive"))
      (node (ref "R24") (pin "1") (pinfunction "1_1") (pintype "passive"))
      (node (ref "R28") (pin "1") (pinfunction "1_1") (pintype "passive"))
      (node (ref "SW2") (pin "1") (pinfunction "1_1") (pintype "passive"))
      (node (ref "SW2") (pin "2") (pinfunction "2_2") (pintype "passive"))
    )
    (net (code "40") (name "/CON_USB_N") (class "Default")
      (node (ref "J3") (pin "2") (pinfunction "2_2") (pintype "passive"))
      (node (ref "R7") (pin "1") (pinfunction "1_1") (pintype "passive"))
      (node (ref "Z1") (pin "2") (pinfunction "2_2") (pintype "passive"))
    )
    (net (code "41") (name "/CON_USB_P") (class "Default")
      (node (ref "J3") (pin "3") (pinfunction "3_3") (pintype "passive"))
      (node (ref "R8") (pin "1") (pinfunction "1_1") (pintype "passive"))
      (node (ref "Z2") (pin "2") (pinfunction "2_2") (pintype "passive"))
    )
    (net (code "42") (name "/IO0") (class "Default")
      (node (ref "J10") (pin "1") (pinfunction "1_1") (pintype "passive"))
      (node (ref "R11") (pin "2") (pinfunction "2_2") (pintype "passive"))
      (node (ref "U3") (pin "2") (pinfunction "(PCINT16/RXD)_PD0_2") (pintype "passive"))
    )
    (net (code "43") (name "/IO1") (class "Default")
      (node (ref "J10") (pin "2") (pinfunction "2_2") (pintype "passive"))
      (node (ref "R12") (pin "2") (pinfunction "2_2") (pintype "passive"))
      (node (ref "U3") (pin "3") (pinfunction "(PCINT17/TXD)_PD1_3") (pintype "passive"))
    )
    (net (code "44") (name "/IO2") (class "Default")
      (node (ref "J10") (pin "3") (pinfunction "3_3") (pintype "passive"))
      (node (ref "U3") (pin "4") (pinfunction "(PCINT17/TXD)_PD1_4") (pintype "passive"))
    )
    (net (code "45") (name "/IO3") (class "Default")
      (node (ref "J10") (pin "4") (pinfunction "4_4") (pintype "passive"))
      (node (ref "U3") (pin "5") (pinfunction "(PCINT19/OC2B/INT1)_PD3_5") (pintype "passive"))
    )
    (net (code "46") (name "/IO4") (class "Default")
      (node (ref "J10") (pin "5") (pinfunction "5_5") (pintype "passive"))
      (node (ref "U3") (pin "6") (pinfunction "(PCINT20/XCK/T0)_PD4_6") (pintype "passive"))
    )
    (net (code "47") (name "/IO5") (class "Default")
      (node (ref "J10") (pin "6") (pinfunction "6_6") (pintype "passive"))
      (node (ref "U3") (pin "11") (pinfunction "(PCINT6/XTAL1/TOSC1)_PB6_11") (pintype "passive"))
    )
    (net (code "48") (name "/IO6") (class "Default")
      (node (ref "J10") (pin "7") (pinfunction "7_7") (pintype "passive"))
      (node (ref "U3") (pin "12") (pinfunction "(PCINT22/OC0A/AIN0)_PD6_12") (pintype "passive"))
    )
    (net (code "49") (name "/IO7") (class "Default")
      (node (ref "J10") (pin "8") (pinfunction "8_8") (pintype "passive"))
      (node (ref "U3") (pin "13") (pinfunction "(PCINT23/AIN1)_PD7_13") (pintype "passive"))
    )
    (net (code "50") (name "/IO8") (class "Default")
      (node (ref "J6") (pin "1") (pinfunction "1_1") (pintype "passive"))
      (node (ref "R25") (pin "2") (pinfunction "2_2") (pintype "passive"))
      (node (ref "U3") (pin "14") (pinfunction "(PCINT23/AIN1)_PD7_14") (pintype "passive"))
    )
    (net (code "51") (name "/IO9") (class "Default")
      (node (ref "J6") (pin "2") (pinfunction "2_2") (pintype "passive"))
      (node (ref "U3") (pin "15") (pinfunction "(OC1A/PCINT1)_PB1_15") (pintype "passive"))
    )
    (net (code "52") (name "/MISO") (class "Default")
      (node (ref "J4") (pin "1") (pinfunction "1_1") (pintype "passive"))
      (node (ref "J6") (pin "5") (pinfunction "5_5") (pintype "passive"))
      (node (ref "U3") (pin "18") (pinfunction "(MISO/PCINT4)_PB4_18") (pintype "passive"))
    )
    (net (code "53") (name "/MOSI") (class "Default")
      (node (ref "J4") (pin "4") (pinfunction "4_4") (pintype "passive"))
      (node (ref "J6") (pin "4") (pinfunction "4_4") (pintype "passive"))
      (node (ref "U3") (pin "17") (pinfunction "(MOSI/OC2A/PCINT3)_PB3_17") (pintype "passive"))
    )
    (net (code "54") (name "/SCK") (class "Default")
      (node (ref "J4") (pin "3") (pinfunction "3_3") (pintype "passive"))
      (node (ref "J6") (pin "6") (pinfunction "6_6") (pintype "passive"))
      (node (ref "R16") (pin "2") (pinfunction "2_2") (pintype "passive"))
      (node (ref "U4") (pin "1") (pinfunction "1_1") (pintype "passive"))
      (node (ref "U4") (pin "2") (pinfunction "2_2") (pintype "passive"))
    )
    (net (code "55") (name "/SCK_R") (class "Default")
      (node (ref "R16") (pin "1") (pinfunction "1_1") (pintype "passive"))
      (node (ref "U3") (pin "19") (pinfunction "(SCK/PCINT5)_PB5_19") (pintype "passive"))
    )
    (net (code "56") (name "/SS") (class "Default")
      (node (ref "J6") (pin "3") (pinfunction "3_3") (pintype "passive"))
      (node (ref "U3") (pin "16") (pinfunction "(SS/OC1B/PCINT2)_PB2_16") (pintype "passive"))
    )
    (net (code "57") (name "/USB_N") (class "Default")
      (node (ref "R7") (pin "2") (pinfunction "2_2") (pintype "passive"))
      (node (ref "U1") (pin "30") (pinfunction "D-_30") (pintype "passive"))
    )
    (net (code "58") (name "/USB_P") (class "Default")
      (node (ref "R8") (pin "2") (pinfunction "2_2") (pintype "passive"))
      (node (ref "U1") (pin "29") (pinfunction "D+_29") (pintype "passive"))
    )
    (net (code "59") (name "/USER_BUTTON") (class "Default")
      (node (ref "R22") (pin "1") (pinfunction "1_1") (pintype "passive"))
      (node (ref "R26") (pin "1") (pinfunction "1_1") (pintype "passive"))
      (node (ref "SW1") (pin "1") (pinfunction "1_1") (pintype "passive"))
      (node (ref "SW1") (pin "2") (pinfunction "2_2") (pintype "passive"))
    )
    (net (code "60") (name "/USER_BUTTON_BUF") (class "Default")
      (node (ref "C31") (pin "2") (pinfunction "2_2") (pintype "passive"))
      (node (ref "R26") (pin "2") (pinfunction "2_2") (pintype "passive"))
      (node (ref "U5") (pin "1") (pinfunction "1_1") (pintype "passive"))
      (node (ref "U5") (pin "2") (pinfunction "2_2") (pintype "passive"))
    )
    (net (code "61") (name "GND") (class "Default")
      (node (ref "C1") (pin "2") (pinfunction "2_2") (pintype "passive"))
      (node (ref "C10") (pin "1") (pinfunction "1_1") (pintype "passive"))
      (node (ref "C12") (pin "1") (pinfunction "1_1") (pintype "passive"))
      (node (ref "C13") (pin "2") (pinfunction "2_2") (pintype "passive"))
      (node (ref "C14") (pin "1") (pinfunction "1_1") (pintype "passive"))
      (node (ref "C15") (pin "1") (pinfunction "1_1") (pintype "passive"))
      (node (ref "C16") (pin "1") (pinfunction "1_1") (pintype "passive"))
      (node (ref "C17") (pin "1") (pinfunction "1_1") (pintype "passive"))
      (node (ref "C18") (pin "1") (pinfunction "1_1") (pintype "passive"))
      (node (ref "C19") (pin "1") (pinfunction "1_1") (pintype "passive"))
      (node (ref "C2") (pin "2") (pinfunction "2_2") (pintype "passive"))
      (node (ref "C20") (pin "1") (pinfunction "1_1") (pintype "passive"))
      (node (ref "C21") (pin "1") (pinfunction "1_1") (pintype "passive"))
      (node (ref "C22") (pin "1") (pinfunction "1_1") (pintype "passive"))
      (node (ref "C23") (pin "1") (pinfunction "1_1") (pintype "passive"))
      (node (ref "C24") (pin "1") (pinfunction "1_1") (pintype "passive"))
      (node (ref "C25") (pin "1") (pinfunction "1_1") (pintype "passive"))
      (node (ref "C26") (pin "1") (pinfunction "1_1") (pintype "passive"))
      (node (ref "C27") (pin "1") (pinfunction "1_1") (pintype "passive"))
      (node (ref "C28") (pin "1") (pinfunction "1_1") (pintype "passive"))
      (node (ref "C29") (pin "1") (pinfunction "1_1") (pintype "passive"))
      (node (ref "C3") (pin "2") (pinfunction "2_2") (pintype "passive"))
      (node (ref "C30") (pin "1") (pinfunction "1_1") (pintype "passive"))
      (node (ref "C31") (pin "1") (pinfunction "1_1") (pintype "passive"))
      (node (ref "C32") (pin "1") (pinfunction "1_1") (pintype "passive"))
      (node (ref "C33") (pin "1") (pinfunction "1_1") (pintype "passive"))
      (node (ref "C4") (pin "1") (pinfunction "1_1") (pintype "passive"))
      (node (ref "C5") (pin "2") (pinfunction "2_2") (pintype "passive"))
      (node (ref "C6") (pin "2") (pinfunction "2_2") (pintype "passive"))
      (node (ref "C7") (pin "1") (pinfunction "1_1") (pintype "passive"))
      (node (ref "C8") (pin "1") (pinfunction "1_1") (pintype "passive"))
      (node (ref "C9") (pin "1") (pinfunction "1_1") (pintype "passive"))
      (node (ref "D4") (pin "1") (pinfunction "Cathode_1") (pintype "passive"))
      (node (ref "J2") (pin "6") (pinfunction "6_6") (pintype "passive"))
      (node (ref "J3") (pin "10") (pinfunction "10_10") (pintype "passive"))
      (node (ref "J3") (pin "11") (pinfunction "11_11") (pintype "passive"))
      (node (ref "J3") (pin "5") (pinfunction "5_5") (pintype "passive"))
      (node (ref "J3") (pin "6") (pinfunction "6_6") (pintype "passive"))
      (node (ref "J3") (pin "7") (pinfunction "7_7") (pintype "passive"))
      (node (ref "J3") (pin "8") (pinfunction "8_8") (pintype "passive"))
      (node (ref "J3") (pin "9") (pinfunction "9_9") (pintype "passive"))
      (node (ref "J4") (pin "6") (pinfunction "6_6") (pintype "passive"))
      (node (ref "J6") (pin "7") (pinfunction "7_7") (pintype "passive"))
      (node (ref "J7") (pin "1") (pinfunction "1_1") (pintype "passive"))
      (node (ref "J8") (pin "6") (pinfunction "6_6") (pintype "passive"))
      (node (ref "J8") (pin "7") (pinfunction "7_7") (pintype "passive"))
      (node (ref "MH1") (pin "1") (pinfunction "1_1") (pintype "passive"))
      (node (ref "MH2") (pin "1") (pinfunction "1_1") (pintype "passive"))
      (node (ref "MH3") (pin "1") (pinfunction "1_1") (pintype "passive"))
      (node (ref "R13") (pin "1") (pinfunction "1_1") (pintype "passive"))
      (node (ref "R9") (pin "2") (pinfunction "2_2") (pintype "passive"))
      (node (ref "SW1") (pin "3") (pinfunction "3_3") (pintype "passive"))
      (node (ref "SW1") (pin "4") (pinfunction "4_4") (pintype "passive"))
      (node (ref "SW2") (pin "3") (pinfunction "3_3") (pintype "passive"))
      (node (ref "SW2") (pin "4") (pinfunction "4_4") (pintype "passive"))
      (node (ref "U1") (pin "28") (pinfunction "UGND_28") (pintype "passive"))
      (node (ref "U1") (pin "3") (pinfunction "GND_3") (pintype "passive"))
      (node (ref "U2") (pin "3") (pinfunction "GND_3") (pintype "passive"))
      (node (ref "U2") (pin "6") (pinfunction "EPAD_6") (pintype "passive"))
      (node (ref "U3") (pin "22") (pinfunction "GND_2_22") (pintype "passive"))
      (node (ref "U3") (pin "8") (pinfunction "GND_1_8") (pintype "passive"))
      (node (ref "U4") (pin "3") (pinfunction "3_3") (pintype "passive"))
      (node (ref "U5") (pin "3") (pinfunction "3_3") (pintype "passive"))
      (node (ref "U6") (pin "3") (pinfunction "3_3") (pintype "passive"))
      (node (ref "U7") (pin "3") (pinfunction "3_3") (pintype "passive"))
      (node (ref "Z1") (pin "1") (pinfunction "1_1") (pintype "passive"))
      (node (ref "Z2") (pin "1") (pinfunction "1_1") (pintype "passive"))
    )
    (net (code "62") (name "Net-(C11-Pad2)") (class "Default")
      (node (ref "C11") (pin "2") (pinfunction "2_2") (pintype "passive"))
      (node (ref "JP2") (pin "1") (pinfunction "1_1") (pintype "passive"))
    )
    (net (code "63") (name "Net-(D1-Anode)") (class "Default")
      (node (ref "D1") (pin "2") (pinfunction "Anode_2") (pintype "passive"))
      (node (ref "R2") (pin "1") (pinfunction "1_1") (pintype "passive"))
    )
    (net (code "64") (name "Net-(D2-Anode)") (class "Default")
      (node (ref "D2") (pin "2") (pinfunction "Anode_2") (pintype "passive"))
      (node (ref "R3") (pin "1") (pinfunction "1_1") (pintype "passive"))
    )
    (net (code "65") (name "Net-(D3-Anode)") (class "Default")
      (node (ref "D3") (pin "2") (pinfunction "Anode_2") (pintype "passive"))
      (node (ref "R18") (pin "1") (pinfunction "1_1") (pintype "passive"))
    )
    (net (code "66") (name "Net-(D3-Cathode)") (class "Default")
      (node (ref "D3") (pin "1") (pinfunction "Cathode_1") (pintype "passive"))
      (node (ref "U4") (pin "4") (pinfunction "4_4") (pintype "passive"))
    )
    (net (code "67") (name "Net-(D4-Anode)") (class "Default")
      (node (ref "D4") (pin "2") (pinfunction "Anode_2") (pintype "passive"))
      (node (ref "R20") (pin "1") (pinfunction "1_1") (pintype "passive"))
    )
    (net (code "68") (name "Net-(D5-Anode)") (class "Default")
      (node (ref "D5") (pin "2") (pinfunction "Anode_2") (pintype "passive"))
      (node (ref "R23") (pin "1") (pinfunction "1_1") (pintype "passive"))
      (node (ref "R27") (pin "1") (pinfunction "1_1") (pintype "passive"))
    )
    (net (code "69") (name "Net-(J3-Pad4)") (class "Default")
      (node (ref "J3") (pin "4") (pinfunction "4_4") (pintype "passive"))
      (node (ref "R9") (pin "1") (pinfunction "1_1") (pintype "passive"))
    )
    (net (code "70") (name "Net-(JP2-Pad3)") (class "Default")
      (node (ref "JP2") (pin "3") (pinfunction "3_3") (pintype "passive"))
      (node (ref "R13") (pin "2") (pinfunction "2_2") (pintype "passive"))
    )
    (net (code "71") (name "Net-(R25-Pad1)") (class "Default")
      (node (ref "R25") (pin "1") (pinfunction "1_1") (pintype "passive"))
      (node (ref "U5") (pin "4") (pinfunction "4_4") (pintype "passive"))
    )
    (net (code "72") (name "unconnected-(J8-Pad1)") (class "Default")
      (node (ref "J8") (pin "1") (pinfunction "1_1") (pintype "passive+no_connect"))
    )
    (net (code "73") (name "unconnected-(J8-Pad8)") (class "Default")
      (node (ref "J8") (pin "8") (pinfunction "8_8") (pintype "passive+no_connect"))
    )
    (net (code "74") (name "unconnected-(MH4-Pad1)") (class "Default")
      (node (ref "MH4") (pin "1") (pinfunction "1_1") (pintype "passive+no_connect"))
    )
    (net (code "75") (name "unconnected-(U1-(AIN0_{slash}_INT1)_PD1-Pad7)") (class "Default")
      (node (ref "U1") (pin "7") (pinfunction "(AIN0_/_INT1)_PD1_7") (pintype "passive+no_connect"))
    )
    (net (code "76") (name "unconnected-(U1-(INT4_{slash}_ICP1_{slash}_CLKO)_PC7-Pad22)") (class "Default")
      (node (ref "U1") (pin "22") (pinfunction "(INT4_/_ICP1_/_CLKO)_PC7_22") (pintype "passive+no_connect"))
    )
    (net (code "77") (name "unconnected-(U1-(OC.0B_{slash}_INT0)_PD0-Pad6)") (class "Default")
      (node (ref "U1") (pin "6") (pinfunction "(OC.0B_/_INT0)_PD0_6") (pintype "passive+no_connect"))
    )
    (net (code "78") (name "unconnected-(U1-(OC.1A_{slash}_PCINT8)_PC6-Pad23)") (class "Default")
      (node (ref "U1") (pin "23") (pinfunction "(OC.1A_/_PCINT8)_PC6_23") (pintype "passive+no_connect"))
    )
    (net (code "79") (name "unconnected-(U1-(PCINT10)_PC4-Pad26)") (class "Default")
      (node (ref "U1") (pin "26") (pinfunction "(PCINT10)_PC4_26") (pintype "passive+no_connect"))
    )
    (net (code "80") (name "unconnected-(U1-(PCINT11_{slash}AIN2)_PC2-Pad5)") (class "Default")
      (node (ref "U1") (pin "5") (pinfunction "(PCINT11_/AIN2)_PC2_5") (pintype "passive+no_connect"))
    )
    (net (code "81") (name "unconnected-(U1-(_PCINT9{slash}_OC.1B)_PC5-Pad25)") (class "Default")
      (node (ref "U1") (pin "25") (pinfunction "(_PCINT9/_OC.1B)_PC5_25") (pintype "passive+no_connect"))
    )
    (net (code "82") (name "unconnected-(U1-(~{RTS}__{slash}_AIN5_{slash}_INT6)_PD6-Pad12)") (class "Default")
      (node (ref "U1") (pin "12") (pinfunction "(~{RTS}__/_AIN5_/_INT6)_PD6_12") (pintype "passive+no_connect"))
    )
    (net (code "83") (name "unconnected-(U1-(~{SS}_{slash}_PCINT0)_PB0-Pad14)") (class "Default")
      (node (ref "U1") (pin "14") (pinfunction "(~{SS}_/_PCINT0)_PB0_14") (pintype "passive"))
    )
  )
)
